# testador_arduino_r00.net
KiCad netlist of a schematic drawn in EAGLE
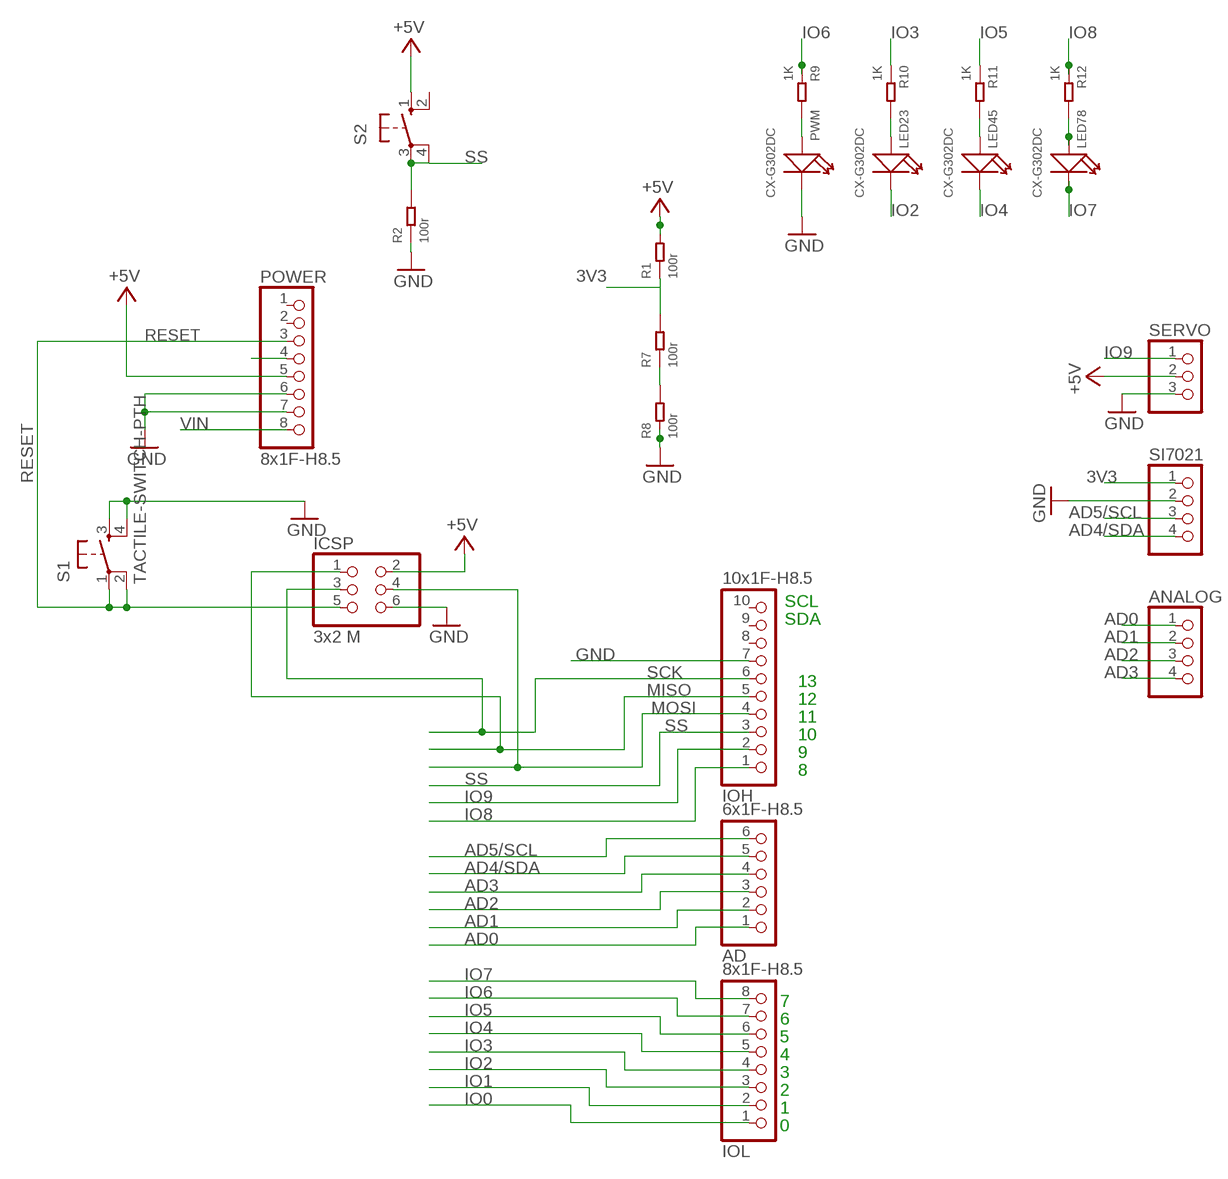
[diagram p0: schematic, sheet 1]

(export (version "E")
  (design (tool "Eeschema 10.0.6"))
  (components
    (comp (ref "AD")
      (value "6x1F-H8.5")
      (footprint "eagle-import:1X06")
      (libsource (lib "eagle-import") (part "PINHD-1X6"))
    )
    (comp (ref "ANALOG")
      (value "PINHD-1X4")
      (footprint "eagle-import:1X04")
      (libsource (lib "eagle-import") (part "PINHD-1X4"))
    )
    (comp (ref "ICSP")
      (value "3x2 M")
      (footprint "eagle-import:2X03")
      (libsource (lib "eagle-import") (part "PINHD-2X3"))
    )
    (comp (ref "IOH")
      (value "10x1F-H8.5")
      (footprint "eagle-import:1X10")
      (libsource (lib "eagle-import") (part "PINHD-1X10_ARD"))
    )
    (comp (ref "IOL")
      (value "8x1F-H8.5")
      (footprint "eagle-import:1X08")
      (libsource (lib "eagle-import") (part "PINHD-1X8"))
    )
    (comp (ref "LED23")
      (value "CX-G302DC")
      (footprint "eagle-import:LED2-2.54-D3.0MM")
      (libsource (lib "eagle-import") (part "DIP-LED-GREEN-GREEN(2P-D3MM)"))
    )
    (comp (ref "LED45")
      (value "CX-G302DC")
      (footprint "eagle-import:LED2-2.54-D3.0MM")
      (libsource (lib "eagle-import") (part "DIP-LED-GREEN-GREEN(2P-D3MM)"))
    )
    (comp (ref "LED78")
      (value "CX-G302DC")
      (footprint "eagle-import:LED2-2.54-D3.0MM")
      (libsource (lib "eagle-import") (part "DIP-LED-GREEN-GREEN(2P-D3MM)"))
    )
    (comp (ref "POWER")
      (value "8x1F-H8.5")
      (footprint "eagle-import:1X08")
      (libsource (lib "eagle-import") (part "PINHD-1X8"))
    )
    (comp (ref "PWM")
      (value "CX-G302DC")
      (footprint "eagle-import:LED2-2.54-D3.0MM")
      (libsource (lib "eagle-import") (part "DIP-LED-GREEN-GREEN(2P-D3MM)"))
    )
    (comp (ref "R1")
      (value "100r")
      (footprint "eagle-import:PR-D2.3XL6.5MM")
      (fields (field (name "MPN") "FHCFR-1/4W-102J"))
      (libsource (lib "eagle-import") (part "DIP-RES-1K-5%-1/4W(PR-D2.3XL6.5MM)"))
    )
    (comp (ref "R2")
      (value "100r")
      (footprint "eagle-import:PR-D2.3XL6.5MM")
      (fields (field (name "MPN") "FHCFR-1/4W-102J"))
      (libsource (lib "eagle-import") (part "DIP-RES-1K-5%-1/4W(PR-D2.3XL6.5MM)"))
    )
    (comp (ref "R7")
      (value "100r")
      (footprint "eagle-import:PR-D2.3XL6.5MM")
      (fields (field (name "MPN") "FHCFR-1/4W-102J"))
      (libsource (lib "eagle-import") (part "DIP-RES-1K-5%-1/4W(PR-D2.3XL6.5MM)"))
    )
    (comp (ref "R8")
      (value "100r")
      (footprint "eagle-import:PR-D2.3XL6.5MM")
      (fields (field (name "MPN") "FHCFR-1/4W-102J"))
      (libsource (lib "eagle-import") (part "DIP-RES-1K-5%-1/4W(PR-D2.3XL6.5MM)"))
    )
    (comp (ref "R9")
      (value "1K")
      (footprint "eagle-import:PR-D2.3XL6.5MM")
      (fields (field (name "MPN") "FHCFR-1/4W-102J"))
      (libsource (lib "eagle-import") (part "DIP-RES-1K-5%-1/4W(PR-D2.3XL6.5MM)"))
    )
    (comp (ref "R10")
      (value "1K")
      (footprint "eagle-import:PR-D2.3XL6.5MM")
      (fields (field (name "MPN") "FHCFR-1/4W-102J"))
      (libsource (lib "eagle-import") (part "DIP-RES-1K-5%-1/4W(PR-D2.3XL6.5MM)"))
    )
    (comp (ref "R11")
      (value "1K")
      (footprint "eagle-import:PR-D2.3XL6.5MM")
      (fields (field (name "MPN") "FHCFR-1/4W-102J"))
      (libsource (lib "eagle-import") (part "DIP-RES-1K-5%-1/4W(PR-D2.3XL6.5MM)"))
    )
    (comp (ref "R12")
      (value "1K")
      (footprint "eagle-import:PR-D2.3XL6.5MM")
      (fields (field (name "MPN") "FHCFR-1/4W-102J"))
      (libsource (lib "eagle-import") (part "DIP-RES-1K-5%-1/4W(PR-D2.3XL6.5MM)"))
    )
    (comp (ref "S1")
      (value "TACTILE-SWITCH-PTH")
      (footprint "eagle-import:TAC-SWITCH-PTH")
      (libsource (lib "eagle-import") (part "TACTILE-SWITCH-PTH"))
    )
    (comp (ref "S2")
      (value "40-XX")
      (footprint "eagle-import:B3F-40XX")
      (fields (field (name "MF") "OMRON COMPONENTS USA") (field (name "MPN") "B3F-4000"))
      (libsource (lib "eagle-import") (part "40-XX"))
    )
    (comp (ref "SERVO")
      (value "PINHD-1X3")
      (footprint "eagle-import:1X03")
      (libsource (lib "eagle-import") (part "PINHD-1X3"))
    )
    (comp (ref "SI7021")
      (value "PINHD-1X4")
      (footprint "eagle-import:1X04")
      (libsource (lib "eagle-import") (part "PINHD-1X4"))
    )
  )
  (nets
    (net (code "1") (name "+5V") (class "Default")
      (node (ref "ICSP") (pin "2") (pinfunction "2_2") (pintype "passive"))
      (node (ref "POWER") (pin "5") (pinfunction "5_5") (pintype "passive"))
      (node (ref "R1") (pin "2") (pinfunction "2_2") (pintype "passive"))
      (node (ref "S2") (pin "1") (pinfunction "S_1") (pintype "passive"))
      (node (ref "SERVO") (pin "2") (pinfunction "2_2") (pintype "passive"))
    )
    (net (code "2") (name "/3V3") (class "Default")
      (node (ref "R1") (pin "1") (pinfunction "1_1") (pintype "passive"))
      (node (ref "R7") (pin "2") (pinfunction "2_2") (pintype "passive"))
      (node (ref "SI7021") (pin "1") (pinfunction "1_1") (pintype "passive"))
    )
    (net (code "3") (name "/AD0") (class "Default")
      (node (ref "AD") (pin "1") (pinfunction "1_1") (pintype "passive"))
      (node (ref "ANALOG") (pin "1") (pinfunction "1_1") (pintype "passive"))
    )
    (net (code "4") (name "/AD1") (class "Default")
      (node (ref "AD") (pin "2") (pinfunction "2_2") (pintype "passive"))
      (node (ref "ANALOG") (pin "2") (pinfunction "2_2") (pintype "passive"))
    )
    (net (code "5") (name "/AD2") (class "Default")
      (node (ref "AD") (pin "3") (pinfunction "3_3") (pintype "passive"))
      (node (ref "ANALOG") (pin "3") (pinfunction "3_3") (pintype "passive"))
    )
    (net (code "6") (name "/AD3") (class "Default")
      (node (ref "AD") (pin "4") (pinfunction "4_4") (pintype "passive"))
      (node (ref "ANALOG") (pin "4") (pinfunction "4_4") (pintype "passive"))
    )
    (net (code "7") (name "/AD4{slash}SDA") (class "Default")
      (node (ref "AD") (pin "5") (pinfunction "5_5") (pintype "passive"))
      (node (ref "SI7021") (pin "4") (pinfunction "4_4") (pintype "passive"))
    )
    (net (code "8") (name "/AD5{slash}SCL") (class "Default")
      (node (ref "AD") (pin "6") (pinfunction "6_6") (pintype "passive"))
      (node (ref "SI7021") (pin "3") (pinfunction "3_3") (pintype "passive"))
    )
    (net (code "9") (name "/IO0") (class "Default")
      (node (ref "IOL") (pin "1") (pinfunction "1_1") (pintype "passive"))
    )
    (net (code "10") (name "/IO1") (class "Default")
      (node (ref "IOL") (pin "2") (pinfunction "2_2") (pintype "passive"))
    )
    (net (code "11") (name "/IO2") (class "Default")
      (node (ref "IOL") (pin "3") (pinfunction "3_3") (pintype "passive"))
      (node (ref "LED23") (pin "K") (pinfunction "-_K") (pintype "passive"))
    )
    (net (code "12") (name "/IO3") (class "Default")
      (node (ref "IOL") (pin "4") (pinfunction "4_4") (pintype "passive"))
      (node (ref "R10") (pin "1") (pinfunction "1_1") (pintype "passive"))
    )
    (net (code "13") (name "/IO4") (class "Default")
      (node (ref "IOL") (pin "5") (pinfunction "5_5") (pintype "passive"))
      (node (ref "LED45") (pin "K") (pinfunction "-_K") (pintype "passive"))
    )
    (net (code "14") (name "/IO5") (class "Default")
      (node (ref "IOL") (pin "6") (pinfunction "6_6") (pintype "passive"))
      (node (ref "R11") (pin "1") (pinfunction "1_1") (pintype "passive"))
    )
    (net (code "15") (name "/IO6") (class "Default")
      (node (ref "IOL") (pin "7") (pinfunction "7_7") (pintype "passive"))
      (node (ref "R9") (pin "1") (pinfunction "1_1") (pintype "passive"))
    )
    (net (code "16") (name "/IO7") (class "Default")
      (node (ref "IOL") (pin "8") (pinfunction "8_8") (pintype "passive"))
      (node (ref "LED78") (pin "K") (pinfunction "-_K") (pintype "passive"))
    )
    (net (code "17") (name "/IO8") (class "Default")
      (node (ref "IOH") (pin "1") (pinfunction "1_1") (pintype "passive"))
      (node (ref "R12") (pin "1") (pinfunction "1_1") (pintype "passive"))
    )
    (net (code "18") (name "/IO9") (class "Default")
      (node (ref "IOH") (pin "2") (pinfunction "2_2") (pintype "passive"))
      (node (ref "SERVO") (pin "1") (pinfunction "1_1") (pintype "passive"))
    )
    (net (code "19") (name "/MISO") (class "Default")
      (node (ref "ICSP") (pin "1") (pinfunction "1_1") (pintype "passive"))
      (node (ref "IOH") (pin "5") (pinfunction "5_5") (pintype "passive"))
    )
    (net (code "20") (name "/MOSI") (class "Default")
      (node (ref "ICSP") (pin "4") (pinfunction "4_4") (pintype "passive"))
      (node (ref "IOH") (pin "4") (pinfunction "4_4") (pintype "passive"))
    )
    (net (code "21") (name "/RESET") (class "Default")
      (node (ref "ICSP") (pin "5") (pinfunction "5_5") (pintype "passive"))
      (node (ref "POWER") (pin "3") (pinfunction "3_3") (pintype "passive"))
      (node (ref "S1") (pin "1") (pinfunction "1_1") (pintype "passive"))
      (node (ref "S1") (pin "2") (pinfunction "2_2") (pintype "passive"))
    )
    (net (code "22") (name "/SCK") (class "Default")
      (node (ref "ICSP") (pin "3") (pinfunction "3_3") (pintype "passive"))
      (node (ref "IOH") (pin "6") (pinfunction "6_6") (pintype "passive"))
    )
    (net (code "23") (name "/SS") (class "Default")
      (node (ref "IOH") (pin "3") (pinfunction "3_3") (pintype "passive"))
      (node (ref "R2") (pin "2") (pinfunction "2_2") (pintype "passive"))
      (node (ref "S2") (pin "3") (pinfunction "P_3") (pintype "passive"))
      (node (ref "S2") (pin "4") (pinfunction "P1_4") (pintype "passive"))
    )
    (net (code "24") (name "/VIN") (class "Default")
      (node (ref "POWER") (pin "8") (pinfunction "8_8") (pintype "passive"))
    )
    (net (code "25") (name "GND") (class "Default")
      (node (ref "ICSP") (pin "6") (pinfunction "6_6") (pintype "passive"))
      (node (ref "IOH") (pin "7") (pinfunction "7_7") (pintype "passive"))
      (node (ref "POWER") (pin "6") (pinfunction "6_6") (pintype "passive"))
      (node (ref "POWER") (pin "7") (pinfunction "7_7") (pintype "passive"))
      (node (ref "PWM") (pin "K") (pinfunction "-_K") (pintype "passive"))
      (node (ref "R2") (pin "1") (pinfunction "1_1") (pintype "passive"))
      (node (ref "R8") (pin "1") (pinfunction "1_1") (pintype "passive"))
      (node (ref "S1") (pin "3") (pinfunction "3_3") (pintype "passive"))
      (node (ref "S1") (pin "4") (pinfunction "4_4") (pintype "passive"))
      (node (ref "SERVO") (pin "3") (pinfunction "3_3") (pintype "passive"))
      (node (ref "SI7021") (pin "2") (pinfunction "2_2") (pintype "passive"))
    )
    (net (code "26") (name "Net-(LED23-+)") (class "Default")
      (node (ref "LED23") (pin "A") (pinfunction "+_A") (pintype "passive"))
      (node (ref "R10") (pin "2") (pinfunction "2_2") (pintype "passive"))
    )
    (net (code "27") (name "Net-(LED45-+)") (class "Default")
      (node (ref "LED45") (pin "A") (pinfunction "+_A") (pintype "passive"))
      (node (ref "R11") (pin "2") (pinfunction "2_2") (pintype "passive"))
    )
    (net (code "28") (name "Net-(LED78-+)") (class "Default")
      (node (ref "LED78") (pin "A") (pinfunction "+_A") (pintype "passive"))
      (node (ref "R12") (pin "2") (pinfunction "2_2") (pintype "passive"))
    )
    (net (code "29") (name "Net-(PWM-+)") (class "Default")
      (node (ref "PWM") (pin "A") (pinfunction "+_A") (pintype "passive"))
      (node (ref "R9") (pin "2") (pinfunction "2_2") (pintype "passive"))
    )
    (net (code "30") (name "Net-(R7-Pad1)") (class "Default")
      (node (ref "R7") (pin "1") (pinfunction "1_1") (pintype "passive"))
      (node (ref "R8") (pin "2") (pinfunction "2_2") (pintype "passive"))
    )
    (net (code "31") (name "unconnected-(IOH-Pad8)") (class "Default")
      (node (ref "IOH") (pin "8") (pinfunction "8_8") (pintype "passive"))
    )
    (net (code "32") (name "unconnected-(IOH-Pad9)") (class "Default")
      (node (ref "IOH") (pin "9") (pinfunction "9_9") (pintype "passive"))
    )
    (net (code "33") (name "unconnected-(IOH-Pad10)") (class "Default")
      (node (ref "IOH") (pin "10") (pinfunction "10_10") (pintype "passive"))
    )
    (net (code "34") (name "unconnected-(POWER-Pad1)") (class "Default")
      (node (ref "POWER") (pin "1") (pinfunction "1_1") (pintype "passive"))
    )
    (net (code "35") (name "unconnected-(POWER-Pad2)") (class "Default")
      (node (ref "POWER") (pin "2") (pinfunction "2_2") (pintype "passive"))
    )
    (net (code "36") (name "unconnected-(POWER-Pad4)") (class "Default")
      (node (ref "POWER") (pin "4") (pinfunction "4_4") (pintype "passive"))
    )
    (net (code "37") (name "unconnected-(S2-S1-Pad2)") (class "Default")
      (node (ref "S2") (pin "2") (pinfunction "S1_2") (pintype "passive"))
    )
  )
)
